# traffic_light.net
KiCad netlist of a schematic drawn in EAGLE
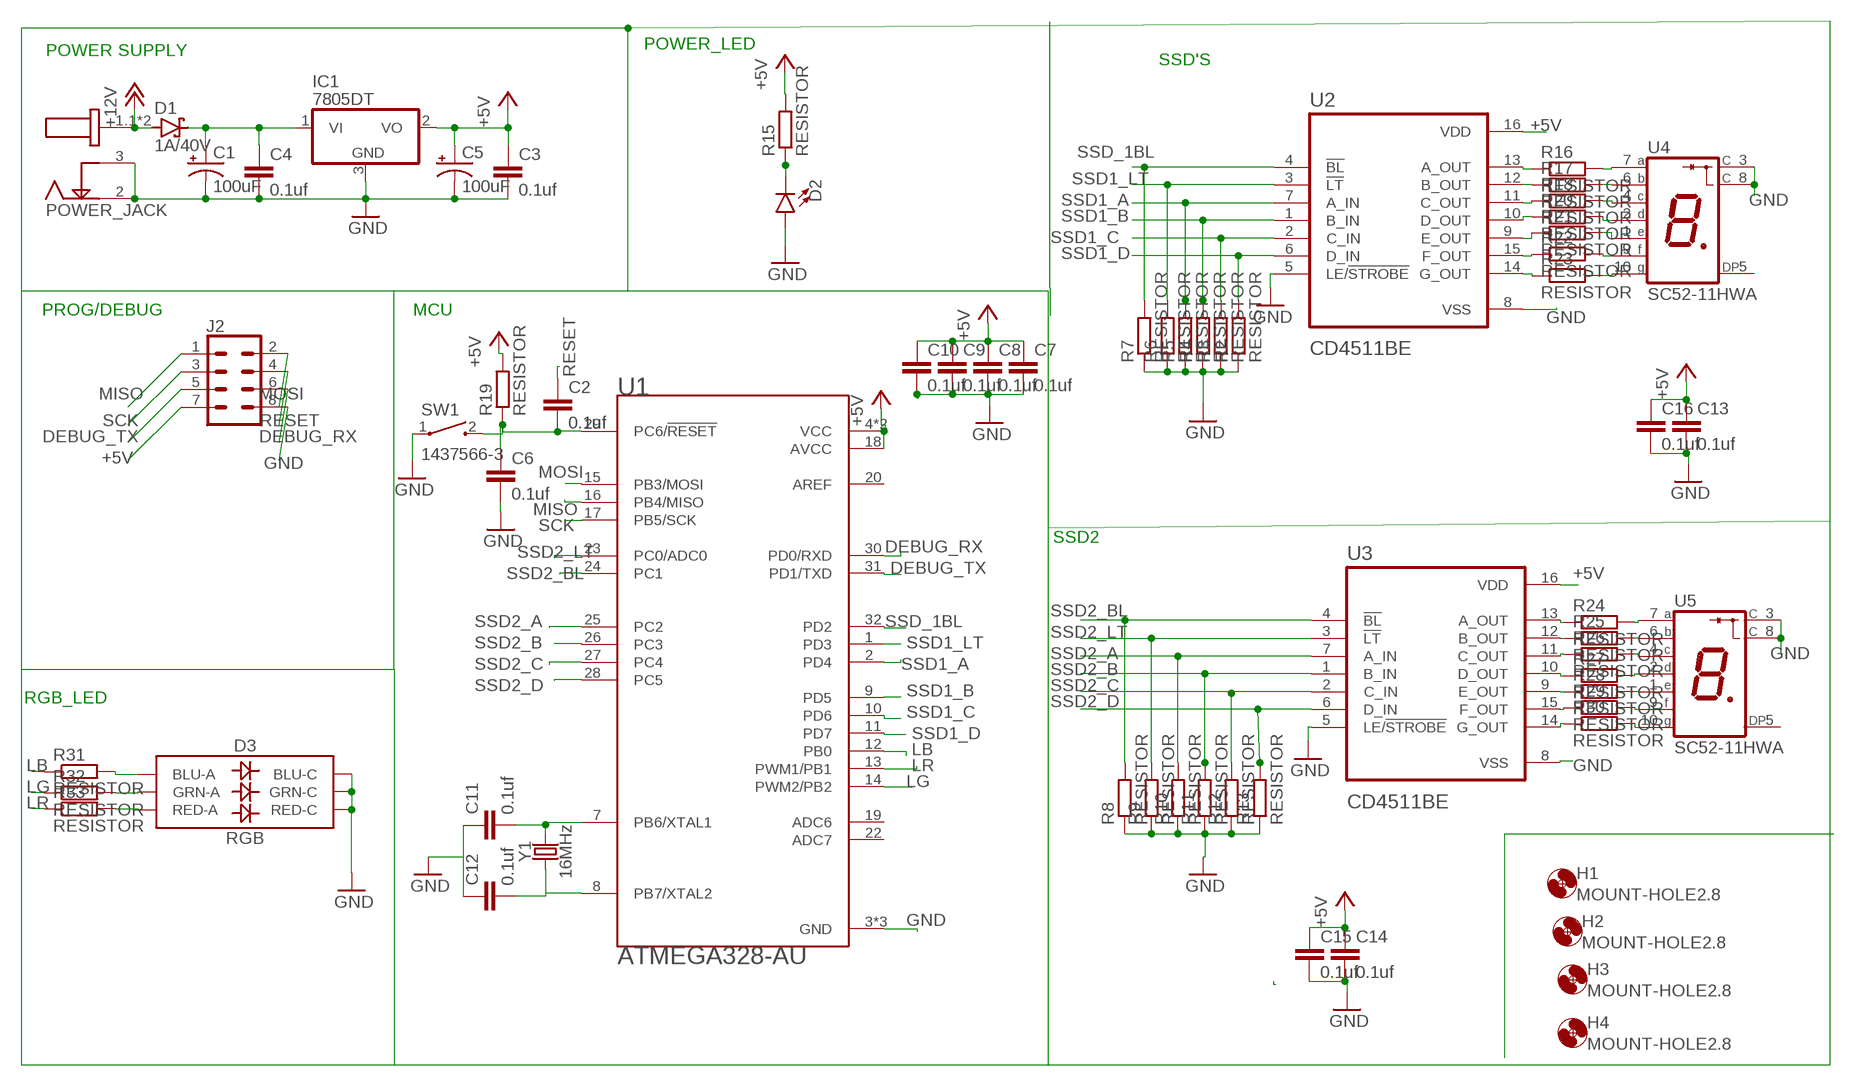
[diagram p0: schematic, sheet 1]

(export (version "E")
  (design (tool "Eeschema 10.0.6"))
  (components
    (comp (ref "C1")
      (value "100uF")
      (footprint "eagle-import:PANASONIC_D")
      (libsource (lib "eagle-import") (part "100UF-POLAR-25V-20%-SMD(ELEC)"))
    )
    (comp (ref "C2")
      (value "0.1uf")
      (footprint "eagle-import:C2.5-2")
      (libsource (lib "eagle-import") (part "C2.5/2"))
    )
    (comp (ref "C3")
      (value "0.1uf")
      (footprint "eagle-import:C2.5-3")
      (libsource (lib "eagle-import") (part "C2,5-3"))
    )
    (comp (ref "C4")
      (value "0.1uf")
      (footprint "eagle-import:C2.5-2")
      (libsource (lib "eagle-import") (part "C2.5/2"))
    )
    (comp (ref "C5")
      (value "100uF")
      (footprint "eagle-import:PANASONIC_D")
      (libsource (lib "eagle-import") (part "100UF-POLAR-25V-20%-SMD(ELEC)"))
    )
    (comp (ref "C6")
      (value "0.1uf")
      (footprint "eagle-import:C2.5-2")
      (libsource (lib "eagle-import") (part "C2.5/2"))
    )
    (comp (ref "C7")
      (value "0.1uf")
      (footprint "eagle-import:C2.5-3")
      (libsource (lib "eagle-import") (part "C2,5-3"))
    )
    (comp (ref "C8")
      (value "0.1uf")
      (footprint "eagle-import:C2.5-3")
      (libsource (lib "eagle-import") (part "C2,5-3"))
    )
    (comp (ref "C9")
      (value "0.1uf")
      (footprint "eagle-import:C2.5-3")
      (libsource (lib "eagle-import") (part "C2,5-3"))
    )
    (comp (ref "C10")
      (value "0.1uf")
      (footprint "eagle-import:C2.5-3")
      (libsource (lib "eagle-import") (part "C2,5-3"))
    )
    (comp (ref "C11")
      (value "0.1uf")
      (footprint "eagle-import:C2.5-2")
      (libsource (lib "eagle-import") (part "C2.5/2"))
    )
    (comp (ref "C12")
      (value "0.1uf")
      (footprint "eagle-import:C2.5-2")
      (libsource (lib "eagle-import") (part "C2.5/2"))
    )
    (comp (ref "C13")
      (value "0.1uf")
      (footprint "eagle-import:C2.5-3")
      (libsource (lib "eagle-import") (part "C2,5-3"))
    )
    (comp (ref "C14")
      (value "0.1uf")
      (footprint "eagle-import:C2.5-3")
      (libsource (lib "eagle-import") (part "C2,5-3"))
    )
    (comp (ref "C15")
      (value "0.1uf")
      (footprint "eagle-import:C2.5-3")
      (libsource (lib "eagle-import") (part "C2,5-3"))
    )
    (comp (ref "C16")
      (value "0.1uf")
      (footprint "eagle-import:C2.5-3")
      (libsource (lib "eagle-import") (part "C2,5-3"))
    )
    (comp (ref "D1")
      (value "1A/40V")
      (footprint "eagle-import:C4111-15")
      (libsource (lib "eagle-import") (part "SCHOTTKY-DIODEC4111-15"))
    )
    (comp (ref "D2")
      (value "LED0603")
      (footprint "eagle-import:LED-0603")
      (libsource (lib "eagle-import") (part "LED0603"))
    )
    (comp (ref "D3")
      (value "RGB")
      (footprint "eagle-import:PLCC-6-LED")
      (libsource (lib "eagle-import") (part "LED-RGBPLCC-6"))
    )
    (comp (ref "H1")
      (value "MOUNT-HOLE2.8")
      (footprint "eagle-import:2,8")
      (libsource (lib "eagle-import") (part "MOUNT-HOLE2.8"))
    )
    (comp (ref "H2")
      (value "MOUNT-HOLE2.8")
      (footprint "eagle-import:2,8")
      (libsource (lib "eagle-import") (part "MOUNT-HOLE2.8"))
    )
    (comp (ref "H3")
      (value "MOUNT-HOLE2.8")
      (footprint "eagle-import:2,8")
      (libsource (lib "eagle-import") (part "MOUNT-HOLE2.8"))
    )
    (comp (ref "H4")
      (value "MOUNT-HOLE2.8")
      (footprint "eagle-import:2,8")
      (libsource (lib "eagle-import") (part "MOUNT-HOLE2.8"))
    )
    (comp (ref "IC1")
      (value "7805DT")
      (footprint "eagle-import:TO252")
      (libsource (lib "eagle-import") (part "78DT05"))
    )
    (comp (ref "J2")
      (value "CONN_04X2")
      (footprint "eagle-import:2X4")
      (libsource (lib "eagle-import") (part "CONN_04X2"))
    )
    (comp (ref "POWER_JACK")
      (value "DCJ200-05-A-XX-X_REVA")
      (footprint "eagle-import:GCT_DCJ200-05-A-XX-X_REVA")
      (fields (field (name "MF") "Global Connector Technology") (field (name "MP") "DCJ200-05-A-K1-A"))
      (libsource (lib "eagle-import") (part "DCJ200-05-A-XX-X_REVA"))
    )
    (comp (ref "R2")
      (value "RESISTOR")
      (footprint "eagle-import:R0603")
      (fields (field (name "MF") "Yageo"))
      (libsource (lib "eagle-import") (part "RESISTOR"))
    )
    (comp (ref "R3")
      (value "RESISTOR")
      (footprint "eagle-import:R0603")
      (fields (field (name "MF") "Yageo"))
      (libsource (lib "eagle-import") (part "RESISTOR"))
    )
    (comp (ref "R4")
      (value "RESISTOR")
      (footprint "eagle-import:R0603")
      (fields (field (name "MF") "Yageo"))
      (libsource (lib "eagle-import") (part "RESISTOR"))
    )
    (comp (ref "R5")
      (value "RESISTOR")
      (footprint "eagle-import:R0603")
      (fields (field (name "MF") "Yageo"))
      (libsource (lib "eagle-import") (part "RESISTOR"))
    )
    (comp (ref "R6")
      (value "RESISTOR")
      (footprint "eagle-import:R0603")
      (fields (field (name "MF") "Yageo"))
      (libsource (lib "eagle-import") (part "RESISTOR"))
    )
    (comp (ref "R7")
      (value "RESISTOR")
      (footprint "eagle-import:R0603")
      (fields (field (name "MF") "Yageo"))
      (libsource (lib "eagle-import") (part "RESISTOR"))
    )
    (comp (ref "R8")
      (value "RESISTOR")
      (footprint "eagle-import:R0603")
      (fields (field (name "MF") "Yageo"))
      (libsource (lib "eagle-import") (part "RESISTOR"))
    )
    (comp (ref "R9")
      (value "RESISTOR")
      (footprint "eagle-import:R0603")
      (fields (field (name "MF") "Yageo"))
      (libsource (lib "eagle-import") (part "RESISTOR"))
    )
    (comp (ref "R10")
      (value "RESISTOR")
      (footprint "eagle-import:R0603")
      (fields (field (name "MF") "Yageo"))
      (libsource (lib "eagle-import") (part "RESISTOR"))
    )
    (comp (ref "R11")
      (value "RESISTOR")
      (footprint "eagle-import:R0603")
      (fields (field (name "MF") "Yageo"))
      (libsource (lib "eagle-import") (part "RESISTOR"))
    )
    (comp (ref "R12")
      (value "RESISTOR")
      (footprint "eagle-import:R0603")
      (fields (field (name "MF") "Yageo"))
      (libsource (lib "eagle-import") (part "RESISTOR"))
    )
    (comp (ref "R13")
      (value "RESISTOR")
      (footprint "eagle-import:R0603")
      (fields (field (name "MF") "Yageo"))
      (libsource (lib "eagle-import") (part "RESISTOR"))
    )
    (comp (ref "R15")
      (value "RESISTOR")
      (footprint "eagle-import:R0603")
      (fields (field (name "MF") "Yageo"))
      (libsource (lib "eagle-import") (part "RESISTOR"))
    )
    (comp (ref "R16")
      (value "RESISTOR")
      (footprint "eagle-import:R0603")
      (fields (field (name "MF") "Yageo"))
      (libsource (lib "eagle-import") (part "RESISTOR"))
    )
    (comp (ref "R17")
      (value "RESISTOR")
      (footprint "eagle-import:R0603")
      (fields (field (name "MF") "Yageo"))
      (libsource (lib "eagle-import") (part "RESISTOR"))
    )
    (comp (ref "R18")
      (value "RESISTOR")
      (footprint "eagle-import:R0603")
      (fields (field (name "MF") "Yageo"))
      (libsource (lib "eagle-import") (part "RESISTOR"))
    )
    (comp (ref "R19")
      (value "RESISTOR")
      (footprint "eagle-import:R0603")
      (fields (field (name "MF") "Yageo"))
      (libsource (lib "eagle-import") (part "RESISTOR"))
    )
    (comp (ref "R20")
      (value "RESISTOR")
      (footprint "eagle-import:R0603")
      (fields (field (name "MF") "Yageo"))
      (libsource (lib "eagle-import") (part "RESISTOR"))
    )
    (comp (ref "R21")
      (value "RESISTOR")
      (footprint "eagle-import:R0603")
      (fields (field (name "MF") "Yageo"))
      (libsource (lib "eagle-import") (part "RESISTOR"))
    )
    (comp (ref "R22")
      (value "RESISTOR")
      (footprint "eagle-import:R0603")
      (fields (field (name "MF") "Yageo"))
      (libsource (lib "eagle-import") (part "RESISTOR"))
    )
    (comp (ref "R23")
      (value "RESISTOR")
      (footprint "eagle-import:R0603")
      (fields (field (name "MF") "Yageo"))
      (libsource (lib "eagle-import") (part "RESISTOR"))
    )
    (comp (ref "R24")
      (value "RESISTOR")
      (footprint "eagle-import:R0603")
      (fields (field (name "MF") "Yageo"))
      (libsource (lib "eagle-import") (part "RESISTOR"))
    )
    (comp (ref "R25")
      (value "RESISTOR")
      (footprint "eagle-import:R0603")
      (fields (field (name "MF") "Yageo"))
      (libsource (lib "eagle-import") (part "RESISTOR"))
    )
    (comp (ref "R26")
      (value "RESISTOR")
      (footprint "eagle-import:R0603")
      (fields (field (name "MF") "Yageo"))
      (libsource (lib "eagle-import") (part "RESISTOR"))
    )
    (comp (ref "R27")
      (value "RESISTOR")
      (footprint "eagle-import:R0603")
      (fields (field (name "MF") "Yageo"))
      (libsource (lib "eagle-import") (part "RESISTOR"))
    )
    (comp (ref "R28")
      (value "RESISTOR")
      (footprint "eagle-import:R0603")
      (fields (field (name "MF") "Yageo"))
      (libsource (lib "eagle-import") (part "RESISTOR"))
    )
    (comp (ref "R29")
      (value "RESISTOR")
      (footprint "eagle-import:R0603")
      (fields (field (name "MF") "Yageo"))
      (libsource (lib "eagle-import") (part "RESISTOR"))
    )
    (comp (ref "R30")
      (value "RESISTOR")
      (footprint "eagle-import:R0603")
      (fields (field (name "MF") "Yageo"))
      (libsource (lib "eagle-import") (part "RESISTOR"))
    )
    (comp (ref "R31")
      (value "RESISTOR")
      (footprint "eagle-import:R0603")
      (fields (field (name "MF") "Yageo"))
      (libsource (lib "eagle-import") (part "RESISTOR"))
    )
    (comp (ref "R32")
      (value "RESISTOR")
      (footprint "eagle-import:R0603")
      (fields (field (name "MF") "Yageo"))
      (libsource (lib "eagle-import") (part "RESISTOR"))
    )
    (comp (ref "R33")
      (value "RESISTOR")
      (footprint "eagle-import:R0603")
      (fields (field (name "MF") "Yageo"))
      (libsource (lib "eagle-import") (part "RESISTOR"))
    )
    (comp (ref "SW1")
      (value "1437566-3")
      (footprint "eagle-import:SW_1437566-3")
      (fields (field (name "MF") "TE Connectivity"))
      (libsource (lib "eagle-import") (part "1437566-3"))
    )
    (comp (ref "U1")
      (value "ATMEGA328-AU")
      (footprint "eagle-import:QFP80P900X900X120-32N")
      (fields (field (name "MF") "Microchip"))
      (libsource (lib "eagle-import") (part "ATMEGA328-AU"))
    )
    (comp (ref "U2")
      (value "CD4511BE")
      (footprint "eagle-import:DIP794W45P254L1969H508Q16")
      (fields (field (name "MF") "Texas Instruments"))
      (libsource (lib "eagle-import") (part "CD4511BE"))
    )
    (comp (ref "U3")
      (value "CD4511BE")
      (footprint "eagle-import:DIP794W45P254L1969H508Q16")
      (fields (field (name "MF") "Texas Instruments"))
      (libsource (lib "eagle-import") (part "CD4511BE"))
    )
    (comp (ref "U4")
      (value "SC52-11HWA")
      (footprint "eagle-import:LED_SC52-11HWA")
      (fields (field (name "MF") "Kingbright"))
      (libsource (lib "eagle-import") (part "SC52-11HWA"))
    )
    (comp (ref "U5")
      (value "SC52-11HWA")
      (footprint "eagle-import:LED_SC52-11HWA")
      (fields (field (name "MF") "Kingbright"))
      (libsource (lib "eagle-import") (part "SC52-11HWA"))
    )
    (comp (ref "Y1")
      (value "16MHz")
      (footprint "eagle-import:HC49US")
      (libsource (lib "eagle-import") (part "CRYSTAL-16MHZPTH-HC49US"))
    )
  )
  (nets
    (net (code "1") (name "+5V") (class "Default")
      (node (ref "C10") (pin "1") (pinfunction "1_1") (pintype "passive"))
      (node (ref "C13") (pin "1") (pinfunction "1_1") (pintype "passive"))
      (node (ref "C14") (pin "1") (pinfunction "1_1") (pintype "passive"))
      (node (ref "C15") (pin "1") (pinfunction "1_1") (pintype "passive"))
      (node (ref "C16") (pin "1") (pinfunction "1_1") (pintype "passive"))
      (node (ref "C3") (pin "1") (pinfunction "1_1") (pintype "passive"))
      (node (ref "C5") (pin "+") (pinfunction "+_+") (pintype "passive"))
      (node (ref "C7") (pin "1") (pinfunction "1_1") (pintype "passive"))
      (node (ref "C8") (pin "1") (pinfunction "1_1") (pintype "passive"))
      (node (ref "C9") (pin "1") (pinfunction "1_1") (pintype "passive"))
      (node (ref "IC1") (pin "2") (pinfunction "VO_2") (pintype "passive"))
      (node (ref "J2") (pin "7") (pinfunction "7_7") (pintype "passive"))
      (node (ref "R15") (pin "2") (pinfunction "2_2") (pintype "passive"))
      (node (ref "R19") (pin "2") (pinfunction "2_2") (pintype "passive"))
      (node (ref "U1") (pin "18") (pinfunction "AVCC_18") (pintype "power_in"))
      (node (ref "U1") (pin "4") (pinfunction "VCC_4") (pintype "power_in"))
      (node (ref "U1") (pin "6") (pinfunction "VCC_6") (pintype "power_in"))
      (node (ref "U2") (pin "16") (pinfunction "VDD_16") (pintype "power_in"))
      (node (ref "U3") (pin "16") (pinfunction "VDD_16") (pintype "power_in"))
    )
    (net (code "2") (name "+12V") (class "Default")
      (node (ref "D1") (pin "A") (pinfunction "A_A") (pintype "passive"))
      (node (ref "POWER_JACK") (pin "1.1") (pinfunction "1_1.1") (pintype "passive"))
      (node (ref "POWER_JACK") (pin "1.2") (pinfunction "1_1.2") (pintype "passive"))
    )
    (net (code "3") (name "/DEBUG_RX") (class "Default")
      (node (ref "J2") (pin "6") (pinfunction "6_6") (pintype "passive"))
      (node (ref "U1") (pin "30") (pinfunction "PD0/RXD_30") (pintype "bidirectional"))
    )
    (net (code "4") (name "/DEBUG_TX") (class "Default")
      (node (ref "J2") (pin "5") (pinfunction "5_5") (pintype "passive"))
      (node (ref "U1") (pin "31") (pinfunction "PD1/TXD_31") (pintype "bidirectional"))
    )
    (net (code "5") (name "/LB") (class "Default")
      (node (ref "R31") (pin "1") (pinfunction "1_1") (pintype "passive"))
      (node (ref "U1") (pin "12") (pinfunction "PB0_12") (pintype "bidirectional"))
    )
    (net (code "6") (name "/LG") (class "Default")
      (node (ref "R32") (pin "1") (pinfunction "1_1") (pintype "passive"))
      (node (ref "U1") (pin "14") (pinfunction "PWM2/PB2_14") (pintype "bidirectional"))
    )
    (net (code "7") (name "/LR") (class "Default")
      (node (ref "R33") (pin "1") (pinfunction "1_1") (pintype "passive"))
      (node (ref "U1") (pin "13") (pinfunction "PWM1/PB1_13") (pintype "bidirectional"))
    )
    (net (code "8") (name "/MISO") (class "Default")
      (node (ref "J2") (pin "1") (pinfunction "1_1") (pintype "passive"))
      (node (ref "U1") (pin "16") (pinfunction "PB4/MISO_16") (pintype "bidirectional"))
    )
    (net (code "9") (name "/MOSI") (class "Default")
      (node (ref "J2") (pin "2") (pinfunction "2_2") (pintype "passive"))
      (node (ref "U1") (pin "15") (pinfunction "PB3/MOSI_15") (pintype "bidirectional"))
    )
    (net (code "10") (name "/RESET") (class "Default")
      (node (ref "C2") (pin "1") (pinfunction "1_1") (pintype "passive"))
      (node (ref "J2") (pin "4") (pinfunction "4_4") (pintype "passive"))
    )
    (net (code "11") (name "/SCK") (class "Default")
      (node (ref "J2") (pin "3") (pinfunction "3_3") (pintype "passive"))
      (node (ref "U1") (pin "17") (pinfunction "PB5/SCK_17") (pintype "bidirectional"))
    )
    (net (code "12") (name "/SSD1_A") (class "Default")
      (node (ref "R5") (pin "2") (pinfunction "2_2") (pintype "passive"))
      (node (ref "U1") (pin "2") (pinfunction "PD4_2") (pintype "bidirectional"))
      (node (ref "U2") (pin "7") (pinfunction "A_IN_7") (pintype "input"))
    )
    (net (code "13") (name "/SSD1_B") (class "Default")
      (node (ref "R4") (pin "2") (pinfunction "2_2") (pintype "passive"))
      (node (ref "U1") (pin "9") (pinfunction "PD5_9") (pintype "bidirectional"))
      (node (ref "U2") (pin "1") (pinfunction "B_IN_1") (pintype "input"))
    )
    (net (code "14") (name "/SSD1_C") (class "Default")
      (node (ref "R3") (pin "2") (pinfunction "2_2") (pintype "passive"))
      (node (ref "U1") (pin "10") (pinfunction "PD6_10") (pintype "bidirectional"))
      (node (ref "U2") (pin "2") (pinfunction "C_IN_2") (pintype "input"))
    )
    (net (code "15") (name "/SSD1_D") (class "Default")
      (node (ref "R2") (pin "2") (pinfunction "2_2") (pintype "passive"))
      (node (ref "U1") (pin "11") (pinfunction "PD7_11") (pintype "bidirectional"))
      (node (ref "U2") (pin "6") (pinfunction "D_IN_6") (pintype "input"))
    )
    (net (code "16") (name "/SSD1_LT") (class "Default")
      (node (ref "R6") (pin "2") (pinfunction "2_2") (pintype "passive"))
      (node (ref "U1") (pin "1") (pinfunction "PD3_1") (pintype "bidirectional"))
      (node (ref "U2") (pin "3") (pinfunction "~{LT}_3") (pintype "input"))
    )
    (net (code "17") (name "/SSD2_A") (class "Default")
      (node (ref "R10") (pin "2") (pinfunction "2_2") (pintype "passive"))
      (node (ref "U1") (pin "25") (pinfunction "PC2_25") (pintype "bidirectional"))
      (node (ref "U3") (pin "7") (pinfunction "A_IN_7") (pintype "input"))
    )
    (net (code "18") (name "/SSD2_B") (class "Default")
      (node (ref "R11") (pin "2") (pinfunction "2_2") (pintype "passive"))
      (node (ref "U1") (pin "26") (pinfunction "PC3_26") (pintype "bidirectional"))
      (node (ref "U3") (pin "1") (pinfunction "B_IN_1") (pintype "input"))
    )
    (net (code "19") (name "/SSD2_BL") (class "Default")
      (node (ref "R8") (pin "2") (pinfunction "2_2") (pintype "passive"))
      (node (ref "U1") (pin "24") (pinfunction "PC1_24") (pintype "bidirectional"))
      (node (ref "U3") (pin "4") (pinfunction "~{BL}_4") (pintype "input"))
    )
    (net (code "20") (name "/SSD2_C") (class "Default")
      (node (ref "R12") (pin "2") (pinfunction "2_2") (pintype "passive"))
      (node (ref "U1") (pin "27") (pinfunction "PC4_27") (pintype "bidirectional"))
      (node (ref "U3") (pin "2") (pinfunction "C_IN_2") (pintype "input"))
    )
    (net (code "21") (name "/SSD2_D") (class "Default")
      (node (ref "R13") (pin "2") (pinfunction "2_2") (pintype "passive"))
      (node (ref "U1") (pin "28") (pinfunction "PC5_28") (pintype "bidirectional"))
      (node (ref "U3") (pin "6") (pinfunction "D_IN_6") (pintype "input"))
    )
    (net (code "22") (name "/SSD2_LT") (class "Default")
      (node (ref "R9") (pin "2") (pinfunction "2_2") (pintype "passive"))
      (node (ref "U1") (pin "23") (pinfunction "PC0/ADC0_23") (pintype "bidirectional"))
      (node (ref "U3") (pin "3") (pinfunction "~{LT}_3") (pintype "input"))
    )
    (net (code "23") (name "/SSD_1BL") (class "Default")
      (node (ref "R7") (pin "2") (pinfunction "2_2") (pintype "passive"))
      (node (ref "U1") (pin "32") (pinfunction "PD2_32") (pintype "bidirectional"))
      (node (ref "U2") (pin "4") (pinfunction "~{BL}_4") (pintype "input"))
    )
    (net (code "24") (name "GND") (class "Default")
      (node (ref "C1") (pin "-") (pinfunction "-_-") (pintype "passive"))
      (node (ref "C10") (pin "2") (pinfunction "2_2") (pintype "passive"))
      (node (ref "C13") (pin "2") (pinfunction "2_2") (pintype "passive"))
      (node (ref "C14") (pin "2") (pinfunction "2_2") (pintype "passive"))
      (node (ref "C15") (pin "2") (pinfunction "2_2") (pintype "passive"))
      (node (ref "C16") (pin "2") (pinfunction "2_2") (pintype "passive"))
      (node (ref "C3") (pin "2") (pinfunction "2_2") (pintype "passive"))
      (node (ref "C4") (pin "2") (pinfunction "2_2") (pintype "passive"))
      (node (ref "C5") (pin "-") (pinfunction "-_-") (pintype "passive"))
      (node (ref "C6") (pin "2") (pinfunction "2_2") (pintype "passive"))
      (node (ref "C7") (pin "2") (pinfunction "2_2") (pintype "passive"))
      (node (ref "C8") (pin "2") (pinfunction "2_2") (pintype "passive"))
      (node (ref "C9") (pin "2") (pinfunction "2_2") (pintype "passive"))
      (node (ref "D2") (pin "A") (pinfunction "A_A") (pintype "passive"))
      (node (ref "D3") (pin "CB") (pinfunction "BLU-C_CB") (pintype "bidirectional"))
      (node (ref "D3") (pin "CG") (pinfunction "GRN-C_CG") (pintype "bidirectional"))
      (node (ref "D3") (pin "CR") (pinfunction "RED-C_CR") (pintype "bidirectional"))
      (node (ref "IC1") (pin "3") (pinfunction "GND_3") (pintype "passive"))
      (node (ref "J2") (pin "8") (pinfunction "8_8") (pintype "passive"))
      (node (ref "POWER_JACK") (pin "2") (pinfunction "2_2") (pintype "passive"))
      (node (ref "POWER_JACK") (pin "3") (pinfunction "3_3") (pintype "passive"))
      (node (ref "R10") (pin "1") (pinfunction "1_1") (pintype "passive"))
      (node (ref "R11") (pin "1") (pinfunction "1_1") (pintype "passive"))
      (node (ref "R12") (pin "1") (pinfunction "1_1") (pintype "passive"))
      (node (ref "R13") (pin "1") (pinfunction "1_1") (pintype "passive"))
      (node (ref "R2") (pin "1") (pinfunction "1_1") (pintype "passive"))
      (node (ref "R3") (pin "1") (pinfunction "1_1") (pintype "passive"))
      (node (ref "R4") (pin "1") (pinfunction "1_1") (pintype "passive"))
      (node (ref "R5") (pin "1") (pinfunction "1_1") (pintype "passive"))
      (node (ref "R6") (pin "1") (pinfunction "1_1") (pintype "passive"))
      (node (ref "R7") (pin "1") (pinfunction "1_1") (pintype "passive"))
      (node (ref "R8") (pin "1") (pinfunction "1_1") (pintype "passive"))
      (node (ref "R9") (pin "1") (pinfunction "1_1") (pintype "passive"))
      (node (ref "SW1") (pin "1") (pinfunction "1_1") (pintype "passive"))
      (node (ref "U1") (pin "21") (pinfunction "GND_21") (pintype "power_in"))
      (node (ref "U1") (pin "3") (pinfunction "GND_3") (pintype "power_in"))
      (node (ref "U1") (pin "5") (pinfunction "GND_5") (pintype "power_in"))
      (node (ref "U2") (pin "5") (pinfunction "LE/~{STROBE}_5") (pintype "input"))
      (node (ref "U2") (pin "8") (pinfunction "VSS_8") (pintype "power_in"))
      (node (ref "U3") (pin "5") (pinfunction "LE/~{STROBE}_5") (pintype "input"))
      (node (ref "U3") (pin "8") (pinfunction "VSS_8") (pintype "power_in"))
      (node (ref "U4") (pin "3") (pinfunction "C_3") (pintype "passive"))
      (node (ref "U4") (pin "8") (pinfunction "C_8") (pintype "passive"))
      (node (ref "U5") (pin "3") (pinfunction "C_3") (pintype "passive"))
      (node (ref "U5") (pin "8") (pinfunction "C_8") (pintype "passive"))
    )
    (net (code "25") (name "Net-(C11-Pad1)") (class "Default")
      (node (ref "C11") (pin "1") (pinfunction "1_1") (pintype "passive"))
      (node (ref "C12") (pin "1") (pinfunction "1_1") (pintype "passive"))
    )
    (net (code "26") (name "Net-(D2-PadC)") (class "Default")
      (node (ref "D2") (pin "C") (pinfunction "C_C") (pintype "passive"))
      (node (ref "R15") (pin "1") (pinfunction "1_1") (pintype "passive"))
    )
    (net (code "27") (name "Net-(D3-BLU-A)") (class "Default")
      (node (ref "D3") (pin "AB") (pinfunction "BLU-A_AB") (pintype "bidirectional"))
      (node (ref "R31") (pin "2") (pinfunction "2_2") (pintype "passive"))
    )
    (net (code "28") (name "Net-(D3-GRN-A)") (class "Default")
      (node (ref "D3") (pin "AG") (pinfunction "GRN-A_AG") (pintype "bidirectional"))
      (node (ref "R32") (pin "2") (pinfunction "2_2") (pintype "passive"))
    )
    (net (code "29") (name "Net-(D3-RED-A)") (class "Default")
      (node (ref "D3") (pin "AR") (pinfunction "RED-A_AR") (pintype "bidirectional"))
      (node (ref "R33") (pin "2") (pinfunction "2_2") (pintype "passive"))
    )
    (net (code "30") (name "Net-(IC1-VI)") (class "Default")
      (node (ref "C1") (pin "+") (pinfunction "+_+") (pintype "passive"))
      (node (ref "C4") (pin "1") (pinfunction "1_1") (pintype "passive"))
      (node (ref "D1") (pin "C") (pinfunction "C_C") (pintype "passive"))
      (node (ref "IC1") (pin "1") (pinfunction "VI_1") (pintype "input"))
    )
    (net (code "31") (name "Net-(R18-Pad2)") (class "Default")
      (node (ref "R18") (pin "2") (pinfunction "2_2") (pintype "passive"))
      (node (ref "U4") (pin "4") (pinfunction "C_4") (pintype "passive"))
    )
    (net (code "32") (name "Net-(R26-Pad2)") (class "Default")
      (node (ref "R26") (pin "2") (pinfunction "2_2") (pintype "passive"))
      (node (ref "U5") (pin "4") (pinfunction "C_4") (pintype "passive"))
    )
    (net (code "33") (name "Net-(U1-PB6{slash}XTAL1)") (class "Default")
      (node (ref "C11") (pin "2") (pinfunction "2_2") (pintype "passive"))
      (node (ref "U1") (pin "7") (pinfunction "PB6/XTAL1_7") (pintype "bidirectional"))
      (node (ref "Y1") (pin "2") (pinfunction "2_2") (pintype "passive"))
    )
    (net (code "34") (name "Net-(U1-PB7{slash}XTAL2)") (class "Default")
      (node (ref "C12") (pin "2") (pinfunction "2_2") (pintype "passive"))
      (node (ref "U1") (pin "8") (pinfunction "PB7/XTAL2_8") (pintype "bidirectional"))
      (node (ref "Y1") (pin "1") (pinfunction "1_1") (pintype "passive"))
    )
    (net (code "35") (name "Net-(U1-PC6{slash}~{RESET})") (class "Default")
      (node (ref "C2") (pin "2") (pinfunction "2_2") (pintype "passive"))
      (node (ref "C6") (pin "1") (pinfunction "1_1") (pintype "passive"))
      (node (ref "R19") (pin "1") (pinfunction "1_1") (pintype "passive"))
      (node (ref "SW1") (pin "2") (pinfunction "2_2") (pintype "passive"))
      (node (ref "U1") (pin "29") (pinfunction "PC6/~{RESET}_29") (pintype "bidirectional"))
    )
    (net (code "36") (name "Net-(U2-A_OUT)") (class "Default")
      (node (ref "R16") (pin "1") (pinfunction "1_1") (pintype "passive"))
      (node (ref "U2") (pin "13") (pinfunction "A_OUT_13") (pintype "output"))
    )
    (net (code "37") (name "Net-(U2-B_OUT)") (class "Default")
      (node (ref "R17") (pin "1") (pinfunction "1_1") (pintype "passive"))
      (node (ref "U2") (pin "12") (pinfunction "B_OUT_12") (pintype "output"))
    )
    (net (code "38") (name "Net-(U2-C_OUT)") (class "Default")
      (node (ref "R18") (pin "1") (pinfunction "1_1") (pintype "passive"))
      (node (ref "U2") (pin "11") (pinfunction "C_OUT_11") (pintype "output"))
    )
    (net (code "39") (name "Net-(U2-D_OUT)") (class "Default")
      (node (ref "R20") (pin "1") (pinfunction "1_1") (pintype "passive"))
      (node (ref "U2") (pin "10") (pinfunction "D_OUT_10") (pintype "output"))
    )
    (net (code "40") (name "Net-(U2-E_OUT)") (class "Default")
      (node (ref "R21") (pin "1") (pinfunction "1_1") (pintype "passive"))
      (node (ref "U2") (pin "9") (pinfunction "E_OUT_9") (pintype "output"))
    )
    (net (code "41") (name "Net-(U2-F_OUT)") (class "Default")
      (node (ref "R22") (pin "1") (pinfunction "1_1") (pintype "passive"))
      (node (ref "U2") (pin "15") (pinfunction "F_OUT_15") (pintype "output"))
    )
    (net (code "42") (name "Net-(U2-G_OUT)") (class "Default")
      (node (ref "R23") (pin "1") (pinfunction "1_1") (pintype "passive"))
      (node (ref "U2") (pin "14") (pinfunction "G_OUT_14") (pintype "output"))
    )
    (net (code "43") (name "Net-(U3-A_OUT)") (class "Default")
      (node (ref "R24") (pin "1") (pinfunction "1_1") (pintype "passive"))
      (node (ref "U3") (pin "13") (pinfunction "A_OUT_13") (pintype "output"))
    )
    (net (code "44") (name "Net-(U3-B_OUT)") (class "Default")
      (node (ref "R25") (pin "1") (pinfunction "1_1") (pintype "passive"))
      (node (ref "U3") (pin "12") (pinfunction "B_OUT_12") (pintype "output"))
    )
    (net (code "45") (name "Net-(U3-C_OUT)") (class "Default")
      (node (ref "R26") (pin "1") (pinfunction "1_1") (pintype "passive"))
      (node (ref "U3") (pin "11") (pinfunction "C_OUT_11") (pintype "output"))
    )
    (net (code "46") (name "Net-(U3-D_OUT)") (class "Default")
      (node (ref "R27") (pin "1") (pinfunction "1_1") (pintype "passive"))
      (node (ref "U3") (pin "10") (pinfunction "D_OUT_10") (pintype "output"))
    )
    (net (code "47") (name "Net-(U3-E_OUT)") (class "Default")
      (node (ref "R28") (pin "1") (pinfunction "1_1") (pintype "passive"))
      (node (ref "U3") (pin "9") (pinfunction "E_OUT_9") (pintype "output"))
    )
    (net (code "48") (name "Net-(U3-F_OUT)") (class "Default")
      (node (ref "R29") (pin "1") (pinfunction "1_1") (pintype "passive"))
      (node (ref "U3") (pin "15") (pinfunction "F_OUT_15") (pintype "output"))
    )
    (net (code "49") (name "Net-(U3-G_OUT)") (class "Default")
      (node (ref "R30") (pin "1") (pinfunction "1_1") (pintype "passive"))
      (node (ref "U3") (pin "14") (pinfunction "G_OUT_14") (pintype "output"))
    )
    (net (code "50") (name "Net-(U4-A)") (class "Default")
      (node (ref "R16") (pin "2") (pinfunction "2_2") (pintype "passive"))
      (node (ref "U4") (pin "7") (pinfunction "A_7") (pintype "passive"))
    )
    (net (code "51") (name "Net-(U4-B)") (class "Default")
      (node (ref "R17") (pin "2") (pinfunction "2_2") (pintype "passive"))
      (node (ref "U4") (pin "6") (pinfunction "B_6") (pintype "passive"))
    )
    (net (code "52") (name "Net-(U4-D)") (class "Default")
      (node (ref "R20") (pin "2") (pinfunction "2_2") (pintype "passive"))
      (node (ref "U4") (pin "2") (pinfunction "D_2") (pintype "passive"))
    )
    (net (code "53") (name "Net-(U4-E)") (class "Default")
      (node (ref "R21") (pin "2") (pinfunction "2_2") (pintype "passive"))
      (node (ref "U4") (pin "1") (pinfunction "E_1") (pintype "passive"))
    )
    (net (code "54") (name "Net-(U4-F)") (class "Default")
      (node (ref "R22") (pin "2") (pinfunction "2_2") (pintype "passive"))
      (node (ref "U4") (pin "9") (pinfunction "F_9") (pintype "passive"))
    )
    (net (code "55") (name "Net-(U4-G)") (class "Default")
      (node (ref "R23") (pin "2") (pinfunction "2_2") (pintype "passive"))
      (node (ref "U4") (pin "10") (pinfunction "G_10") (pintype "passive"))
    )
    (net (code "56") (name "Net-(U5-A)") (class "Default")
      (node (ref "R24") (pin "2") (pinfunction "2_2") (pintype "passive"))
      (node (ref "U5") (pin "7") (pinfunction "A_7") (pintype "passive"))
    )
    (net (code "57") (name "Net-(U5-B)") (class "Default")
      (node (ref "R25") (pin "2") (pinfunction "2_2") (pintype "passive"))
      (node (ref "U5") (pin "6") (pinfunction "B_6") (pintype "passive"))
    )
    (net (code "58") (name "Net-(U5-D)") (class "Default")
      (node (ref "R27") (pin "2") (pinfunction "2_2") (pintype "passive"))
      (node (ref "U5") (pin "2") (pinfunction "D_2") (pintype "passive"))
    )
    (net (code "59") (name "Net-(U5-E)") (class "Default")
      (node (ref "R28") (pin "2") (pinfunction "2_2") (pintype "passive"))
      (node (ref "U5") (pin "1") (pinfunction "E_1") (pintype "passive"))
    )
    (net (code "60") (name "Net-(U5-F)") (class "Default")
      (node (ref "R29") (pin "2") (pinfunction "2_2") (pintype "passive"))
      (node (ref "U5") (pin "9") (pinfunction "F_9") (pintype "passive"))
    )
    (net (code "61") (name "Net-(U5-G)") (class "Default")
      (node (ref "R30") (pin "2") (pinfunction "2_2") (pintype "passive"))
      (node (ref "U5") (pin "10") (pinfunction "G_10") (pintype "passive"))
    )
    (net (code "62") (name "unconnected-(U1-ADC6-Pad19)") (class "Default")
      (node (ref "U1") (pin "19") (pinfunction "ADC6_19") (pintype "bidirectional"))
    )
    (net (code "63") (name "unconnected-(U1-ADC7-Pad22)") (class "Default")
      (node (ref "U1") (pin "22") (pinfunction "ADC7_22") (pintype "bidirectional"))
    )
    (net (code "64") (name "unconnected-(U1-AREF-Pad20)") (class "Default")
      (node (ref "U1") (pin "20") (pinfunction "AREF_20") (pintype "input"))
    )
    (net (code "65") (name "unconnected-(U4-DP-Pad5)") (class "Default")
      (node (ref "U4") (pin "5") (pinfunction "DP_5") (pintype "passive"))
    )
    (net (code "66") (name "unconnected-(U5-DP-Pad5)") (class "Default")
      (node (ref "U5") (pin "5") (pinfunction "DP_5") (pintype "passive"))
    )
  )
)
